# Step_Down.net
KiCad netlist of a schematic drawn in EAGLE
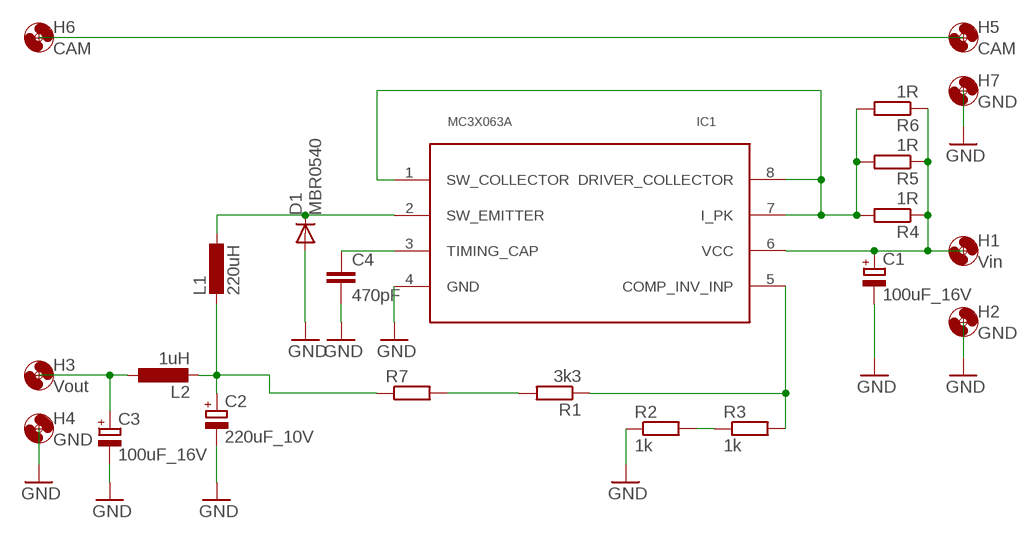
[diagram p0: schematic, sheet 1]

(export (version "E")
  (design (tool "Eeschema 10.0.6"))
  (components
    (comp (ref "C1")
      (value "100uF_16V")
      (footprint "eagle-import:D_7343-31W")
      (libsource (lib "eagle-import") (part "CPOL-EUD/7343-31W"))
    )
    (comp (ref "C2")
      (value "220uF_10V")
      (footprint "eagle-import:D_7343-31W")
      (libsource (lib "eagle-import") (part "CPOL-EUD/7343-31W"))
    )
    (comp (ref "C3")
      (value "100uF_16V")
      (footprint "eagle-import:D_7343-31W")
      (libsource (lib "eagle-import") (part "CPOL-EUD/7343-31W"))
    )
    (comp (ref "C4")
      (value "470pF")
      (footprint "eagle-import:C0805K")
      (libsource (lib "eagle-import") (part "C-EUC0805K"))
    )
    (comp (ref "D1")
      (value "MBR0540")
      (footprint "eagle-import:SOD-123_MINI-SMA")
      (libsource (lib "eagle-import") (part "CGRM400-G1"))
    )
    (comp (ref "H1")
      (value "Vin")
      (footprint "eagle-import:2,8")
      (libsource (lib "eagle-import") (part "MOUNT-HOLE2.8"))
    )
    (comp (ref "H2")
      (value "GND")
      (footprint "eagle-import:2,8")
      (libsource (lib "eagle-import") (part "MOUNT-HOLE2.8"))
    )
    (comp (ref "H3")
      (value "Vout")
      (footprint "eagle-import:2,8")
      (libsource (lib "eagle-import") (part "MOUNT-HOLE2.8"))
    )
    (comp (ref "H4")
      (value "GND")
      (footprint "eagle-import:2,8")
      (libsource (lib "eagle-import") (part "MOUNT-HOLE2.8"))
    )
    (comp (ref "H5")
      (value "CAM")
      (footprint "eagle-import:2,8")
      (libsource (lib "eagle-import") (part "MOUNT-HOLE2.8"))
    )
    (comp (ref "H6")
      (value "CAM")
      (footprint "eagle-import:2,8")
      (libsource (lib "eagle-import") (part "MOUNT-HOLE2.8"))
    )
    (comp (ref "H7")
      (value "GND")
      (footprint "eagle-import:2,8")
      (libsource (lib "eagle-import") (part "MOUNT-HOLE2.8"))
    )
    (comp (ref "IC1")
      (value "MC3X063A")
      (footprint "eagle-import:SO08")
      (libsource (lib "eagle-import") (part "MC3X063A"))
    )
    (comp (ref "L1")
      (value "220uH")
      (footprint "eagle-import:2220")
      (libsource (lib "eagle-import") (part "L-SMD-2220"))
    )
    (comp (ref "L2")
      (value "1uH")
      (footprint "eagle-import:L1812")
      (libsource (lib "eagle-import") (part "L-EUL1812"))
    )
    (comp (ref "R1")
      (value "3k3")
      (footprint "eagle-import:R0805")
      (libsource (lib "eagle-import") (part "R-EU_R0805"))
    )
    (comp (ref "R2")
      (value "1k")
      (footprint "eagle-import:R0805")
      (libsource (lib "eagle-import") (part "R-EU_R0805"))
    )
    (comp (ref "R3")
      (value "1k")
      (footprint "eagle-import:R0805")
      (libsource (lib "eagle-import") (part "R-EU_R0805"))
    )
    (comp (ref "R4")
      (value "1R")
      (footprint "eagle-import:R0805")
      (libsource (lib "eagle-import") (part "R-EU_R0805"))
    )
    (comp (ref "R5")
      (value "1R")
      (footprint "eagle-import:R0805")
      (libsource (lib "eagle-import") (part "R-EU_R0805"))
    )
    (comp (ref "R6")
      (value "1R")
      (footprint "eagle-import:R0805")
      (libsource (lib "eagle-import") (part "R-EU_R0805"))
    )
    (comp (ref "R7")
      (value "R-EU_R1206W")
      (footprint "eagle-import:R1206W")
      (libsource (lib "eagle-import") (part "R-EU_R1206W"))
    )
  )
  (nets
    (net (code "1") (name "GND") (class "Default")
      (node (ref "C1") (pin "-") (pinfunction "-_-") (pintype "passive"))
      (node (ref "C2") (pin "-") (pinfunction "-_-") (pintype "passive"))
      (node (ref "C3") (pin "-") (pinfunction "-_-") (pintype "passive"))
      (node (ref "C4") (pin "2") (pinfunction "2_2") (pintype "passive"))
      (node (ref "D1") (pin "A") (pinfunction "A_A") (pintype "passive"))
      (node (ref "H2") (pin "P$1") (pinfunction "P$1_P$1") (pintype "bidirectional"))
      (node (ref "H4") (pin "P$1") (pinfunction "P$1_P$1") (pintype "bidirectional"))
      (node (ref "H7") (pin "P$1") (pinfunction "P$1_P$1") (pintype "bidirectional"))
      (node (ref "IC1") (pin "4") (pinfunction "GND_4") (pintype "bidirectional"))
      (node (ref "R2") (pin "1") (pinfunction "1_1") (pintype "passive"))
    )
    (net (code "2") (name "Net-(C2-Pad+)") (class "Default")
      (node (ref "C2") (pin "+") (pinfunction "+_+") (pintype "passive"))
      (node (ref "L1") (pin "2") (pinfunction "2_2") (pintype "passive"))
      (node (ref "L2") (pin "2") (pinfunction "2_2") (pintype "passive"))
      (node (ref "R7") (pin "1") (pinfunction "1_1") (pintype "passive"))
    )
    (net (code "3") (name "Net-(C3-Pad+)") (class "Default")
      (node (ref "C3") (pin "+") (pinfunction "+_+") (pintype "passive"))
      (node (ref "H3") (pin "P$1") (pinfunction "P$1_P$1") (pintype "bidirectional"))
      (node (ref "L2") (pin "1") (pinfunction "1_1") (pintype "passive"))
    )
    (net (code "4") (name "Net-(H5-PadP$1)") (class "Default")
      (node (ref "H5") (pin "P$1") (pinfunction "P$1_P$1") (pintype "bidirectional"))
      (node (ref "H6") (pin "P$1") (pinfunction "P$1_P$1") (pintype "bidirectional"))
    )
    (net (code "5") (name "Net-(IC1-COMP_INV_INP)") (class "Default")
      (node (ref "IC1") (pin "5") (pinfunction "COMP_INV_INP_5") (pintype "bidirectional"))
      (node (ref "R1") (pin "1") (pinfunction "1_1") (pintype "passive"))
      (node (ref "R3") (pin "2") (pinfunction "2_2") (pintype "passive"))
    )
    (net (code "6") (name "Net-(IC1-DRIVER_COLLECTOR)") (class "Default")
      (node (ref "IC1") (pin "1") (pinfunction "SW_COLLECTOR_1") (pintype "bidirectional"))
      (node (ref "IC1") (pin "7") (pinfunction "I_PK_7") (pintype "bidirectional"))
      (node (ref "IC1") (pin "8") (pinfunction "DRIVER_COLLECTOR_8") (pintype "bidirectional"))
      (node (ref "R4") (pin "2") (pinfunction "2_2") (pintype "passive"))
      (node (ref "R5") (pin "2") (pinfunction "2_2") (pintype "passive"))
      (node (ref "R6") (pin "2") (pinfunction "2_2") (pintype "passive"))
    )
    (net (code "7") (name "Net-(IC1-SW_EMITTER)") (class "Default")
      (node (ref "D1") (pin "C") (pinfunction "C_C") (pintype "passive"))
      (node (ref "IC1") (pin "2") (pinfunction "SW_EMITTER_2") (pintype "bidirectional"))
      (node (ref "L1") (pin "1") (pinfunction "1_1") (pintype "passive"))
    )
    (net (code "8") (name "Net-(IC1-TIMING_CAP)") (class "Default")
      (node (ref "C4") (pin "1") (pinfunction "1_1") (pintype "passive"))
      (node (ref "IC1") (pin "3") (pinfunction "TIMING_CAP_3") (pintype "bidirectional"))
    )
    (net (code "9") (name "Net-(IC1-VCC)") (class "Default")
      (node (ref "C1") (pin "+") (pinfunction "+_+") (pintype "passive"))
      (node (ref "H1") (pin "P$1") (pinfunction "P$1_P$1") (pintype "bidirectional"))
      (node (ref "IC1") (pin "6") (pinfunction "VCC_6") (pintype "bidirectional"))
      (node (ref "R4") (pin "1") (pinfunction "1_1") (pintype "passive"))
      (node (ref "R5") (pin "1") (pinfunction "1_1") (pintype "passive"))
      (node (ref "R6") (pin "1") (pinfunction "1_1") (pintype "passive"))
    )
    (net (code "10") (name "Net-(R1-Pad2)") (class "Default")
      (node (ref "R1") (pin "2") (pinfunction "2_2") (pintype "passive"))
      (node (ref "R7") (pin "2") (pinfunction "2_2") (pintype "passive"))
    )
    (net (code "11") (name "Net-(R2-Pad2)") (class "Default")
      (node (ref "R2") (pin "2") (pinfunction "2_2") (pintype "passive"))
      (node (ref "R3") (pin "1") (pinfunction "1_1") (pintype "passive"))
    )
  )
)
